# POE.net
KiCad netlist of a schematic drawn in Altium Designer
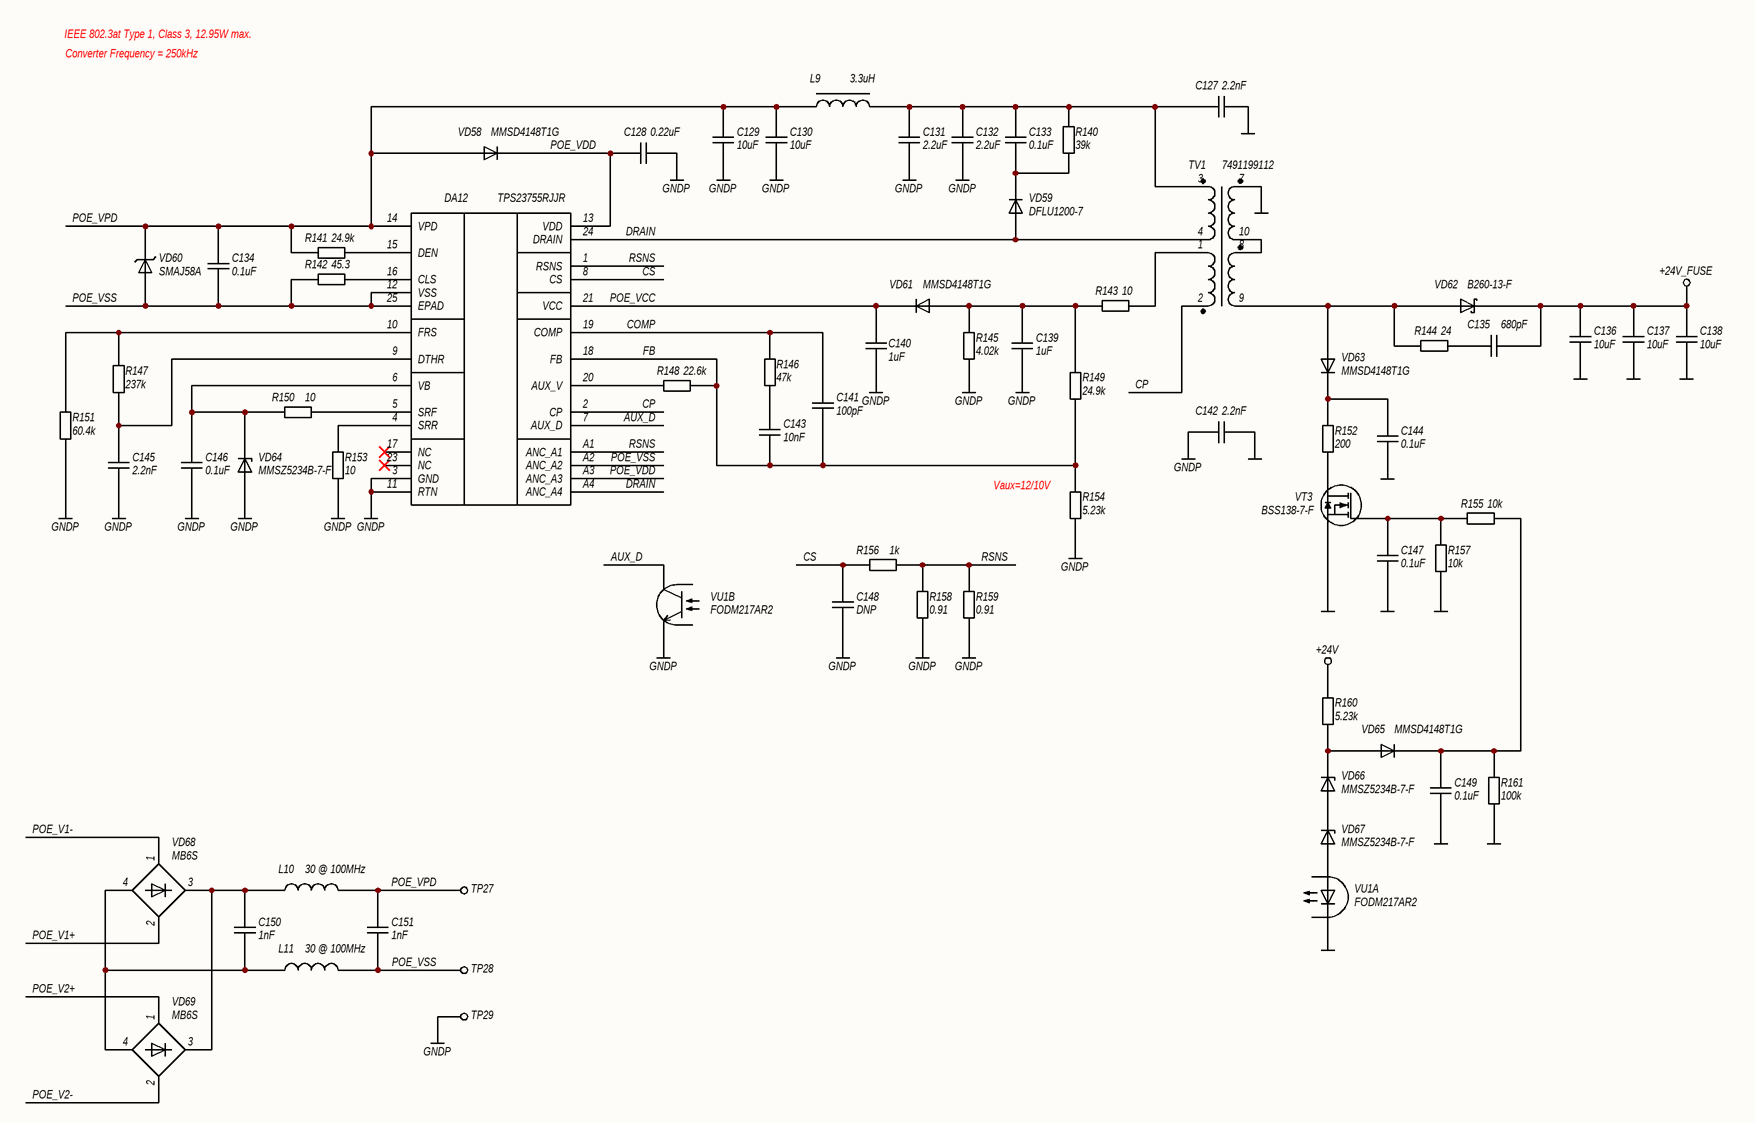
[diagram p0: POE.SchDoc]

(export (version "E")
  (design (tool "Eeschema 10.0.6"))
  (components
    (comp (ref "C127")
      (value "2.2nF")
      (footprint "C1812N")
      (description "Конденсатор")
      (libsource (lib "Components Library") (part "CAP_FIXED"))
    )
    (comp (ref "C128")
      (value "0.22uF")
      (footprint "C0805N")
      (description "Конденсатор")
      (libsource (lib "Components Library") (part "CAP_FIXED"))
    )
    (comp (ref "C129")
      (value "10uF")
      (footprint "C1210N")
      (description "Конденсатор")
      (libsource (lib "Components Library") (part "CAP_FIXED"))
    )
    (comp (ref "C130")
      (value "10uF")
      (footprint "C1210N")
      (description "Конденсатор")
      (libsource (lib "Components Library") (part "CAP_FIXED"))
    )
    (comp (ref "C131")
      (value "2.2uF")
      (footprint "C1210N")
      (description "Конденсатор")
      (libsource (lib "Components Library") (part "CAP_FIXED"))
    )
    (comp (ref "C132")
      (value "2.2uF")
      (footprint "C1210N")
      (description "Конденсатор")
      (libsource (lib "Components Library") (part "CAP_FIXED"))
    )
    (comp (ref "C133")
      (value "0.1uF")
      (footprint "C0805N")
      (description "Конденсатор")
      (libsource (lib "Components Library") (part "CAP_FIXED"))
    )
    (comp (ref "C134")
      (value "0.1uF")
      (footprint "C0805N")
      (description "Конденсатор")
      (libsource (lib "Components Library") (part "CAP_FIXED"))
    )
    (comp (ref "C135")
      (value "680pF")
      (footprint "C0805N")
      (description "Конденсатор")
      (libsource (lib "Components Library") (part "CAP_FIXED"))
    )
    (comp (ref "C136")
      (value "10uF")
      (footprint "C1206N")
      (description "Конденсатор")
      (libsource (lib "Components Library") (part "CAP_FIXED"))
    )
    (comp (ref "C137")
      (value "10uF")
      (footprint "C1206N")
      (description "Конденсатор")
      (libsource (lib "Components Library") (part "CAP_FIXED"))
    )
    (comp (ref "C138")
      (value "10uF")
      (footprint "C1206N")
      (description "Конденсатор")
      (libsource (lib "Components Library") (part "CAP_FIXED"))
    )
    (comp (ref "C139")
      (value "1uF")
      (footprint "C0805N")
      (description "Конденсатор")
      (libsource (lib "Components Library") (part "CAP_FIXED"))
    )
    (comp (ref "C140")
      (value "1uF")
      (footprint "C0805N")
      (description "Конденсатор")
      (libsource (lib "Components Library") (part "CAP_FIXED"))
    )
    (comp (ref "C141")
      (value "100pF")
      (footprint "C0603N")
      (description "Конденсатор")
      (libsource (lib "Components Library") (part "CAP_FIXED"))
    )
    (comp (ref "C142")
      (value "2.2nF")
      (footprint "C1812N")
      (description "Конденсатор")
      (libsource (lib "Components Library") (part "CAP_FIXED"))
    )
    (comp (ref "C143")
      (value "10nF")
      (footprint "C0603N")
      (description "Конденсатор")
      (libsource (lib "Components Library") (part "CAP_FIXED"))
    )
    (comp (ref "C144")
      (value "0.1uF")
      (footprint "C0603N")
      (description "Конденсатор")
      (libsource (lib "Components Library") (part "CAP_FIXED"))
    )
    (comp (ref "C145")
      (value "2.2nF")
      (footprint "C0603N")
      (description "Конденсатор")
      (libsource (lib "Components Library") (part "CAP_FIXED"))
    )
    (comp (ref "C146")
      (value "0.1uF")
      (footprint "C0603N")
      (description "Конденсатор")
      (libsource (lib "Components Library") (part "CAP_FIXED"))
    )
    (comp (ref "C147")
      (value "0.1uF")
      (footprint "C0603N")
      (description "Конденсатор")
      (libsource (lib "Components Library") (part "CAP_FIXED"))
    )
    (comp (ref "C148")
      (value "DNP")
      (footprint "C0603N")
      (description "Конденсатор")
      (libsource (lib "Components Library") (part "CAP_FIXED"))
    )
    (comp (ref "C149")
      (value "0.1uF")
      (footprint "C0603N")
      (description "Конденсатор")
      (libsource (lib "Components Library") (part "CAP_FIXED"))
    )
    (comp (ref "C150")
      (value "1nF")
      (footprint "C0603N")
      (description "Конденсатор")
      (libsource (lib "Components Library") (part "CAP_FIXED"))
    )
    (comp (ref "C151")
      (value "1nF")
      (footprint "C0603N")
      (description "Конденсатор")
      (libsource (lib "Components Library") (part "CAP_FIXED"))
    )
    (comp (ref "DA12")
      (value "TPS23755RJJR")
      (footprint "RJJ0023B (VSON-24 EP)")
      (description "Микросхема PoE 802.3at DC-DC контроллера")
      (libsource (lib "Components Library") (part "TPS23755"))
    )
    (comp (ref "L9")
      (value "3.3uH")
      (footprint "SRN3015")
      (description "Дроссель с магнитопроводом")
      (libsource (lib "Components Library") (part "IND_CORE"))
    )
    (comp (ref "L10")
      (value "30 @ 100MHz")
      (footprint "FB0603N")
      (description "Фильтр ЭМП индуктивный")
      (libsource (lib "Components Library") (part "IND_FILTER"))
    )
    (comp (ref "L11")
      (value "30 @ 100MHz")
      (footprint "FB0603N")
      (description "Фильтр ЭМП индуктивный")
      (libsource (lib "Components Library") (part "IND_FILTER"))
    )
    (comp (ref "R140")
      (value "39k")
      (footprint "R0805N")
      (description "Резистор")
      (libsource (lib "") (part "RES_FIXED_1"))
    )
    (comp (ref "R141")
      (value "24.9k")
      (footprint "R0603N")
      (description "Резистор")
      (libsource (lib "") (part "RES_FIXED_2"))
    )
    (comp (ref "R142")
      (value "45.3")
      (footprint "R0603N")
      (description "Резистор")
      (libsource (lib "") (part "RES_FIXED_2"))
    )
    (comp (ref "R143")
      (value "10")
      (footprint "R0805N")
      (description "Резистор")
      (libsource (lib "") (part "RES_FIXED_2"))
    )
    (comp (ref "R144")
      (value "24")
      (footprint "R1206N")
      (description "Резистор")
      (libsource (lib "Components Library") (part "RES_FIXED"))
    )
    (comp (ref "R145")
      (value "4.02k")
      (footprint "R0603N")
      (description "Резистор")
      (libsource (lib "") (part "RES_FIXED_1"))
    )
    (comp (ref "R146")
      (value "47k")
      (footprint "R0603N")
      (description "Резистор")
      (libsource (lib "") (part "RES_FIXED_3"))
    )
    (comp (ref "R147")
      (value "237k")
      (footprint "R0603N")
      (description "Резистор")
      (libsource (lib "") (part "RES_FIXED_3"))
    )
    (comp (ref "R148")
      (value "22.6k")
      (footprint "R0603N")
      (description "Резистор")
      (libsource (lib "Components Library") (part "RES_FIXED"))
    )
    (comp (ref "R149")
      (value "24.9k")
      (footprint "R0603N")
      (description "Резистор")
      (libsource (lib "") (part "RES_FIXED_1"))
    )
    (comp (ref "R150")
      (value "10")
      (footprint "R0603N")
      (description "Резистор")
      (libsource (lib "") (part "RES_FIXED_2"))
    )
    (comp (ref "R151")
      (value "60.4k")
      (footprint "R0603N")
      (description "Резистор")
      (libsource (lib "") (part "RES_FIXED_1"))
    )
    (comp (ref "R152")
      (value "200")
      (footprint "R2512N")
      (description "Резистор")
      (libsource (lib "") (part "RES_FIXED_1"))
    )
    (comp (ref "R153")
      (value "10")
      (footprint "R0603N")
      (description "Резистор")
      (libsource (lib "") (part "RES_FIXED_1"))
    )
    (comp (ref "R154")
      (value "5.23k")
      (footprint "R0603N")
      (description "Резистор")
      (libsource (lib "") (part "RES_FIXED_1"))
    )
    (comp (ref "R155")
      (value "10k")
      (footprint "R0603N")
      (description "Резистор")
      (libsource (lib "") (part "RES_FIXED_2"))
    )
    (comp (ref "R156")
      (value "1k")
      (footprint "R0603N")
      (description "Резистор")
      (libsource (lib "Components Library") (part "RES_FIXED"))
    )
    (comp (ref "R157")
      (value "10k")
      (footprint "R0603N")
      (description "Резистор")
      (libsource (lib "") (part "RES_FIXED_3"))
    )
    (comp (ref "R158")
      (value "0.91")
      (footprint "R1206N")
      (description "Резистор")
      (libsource (lib "") (part "RES_FIXED_1"))
    )
    (comp (ref "R159")
      (value "0.91")
      (footprint "R1206N")
      (description "Резистор")
      (libsource (lib "") (part "RES_FIXED_1"))
    )
    (comp (ref "R160")
      (value "5.23k")
      (footprint "R0603N")
      (description "Резистор")
      (libsource (lib "") (part "RES_FIXED_1"))
    )
    (comp (ref "R161")
      (value "100k")
      (footprint "R0603N")
      (description "Резистор")
      (libsource (lib "") (part "RES_FIXED_3"))
    )
    (comp (ref "TP27")
      (value "TEST_POINT")
      (footprint "TP_RPAD_0.8MM")
      (description "Контрольная точка")
      (libsource (lib "Components Library") (part "TEST_POINT"))
    )
    (comp (ref "TP28")
      (value "TEST_POINT")
      (footprint "TP_RPAD_0.8MM")
      (description "Контрольная точка")
      (libsource (lib "Components Library") (part "TEST_POINT"))
    )
    (comp (ref "TP29")
      (value "TEST_POINT")
      (footprint "TP_RPAD_0.8MM")
      (description "Контрольная точка")
      (libsource (lib "Components Library") (part "TEST_POINT"))
    )
    (comp (ref "TV1")
      (value "7491199112")
      (footprint "7491199112")
      (description "Трансформатор PoE")
      (libsource (lib "Components Library") (part "7491199112"))
    )
    (comp (ref "VD58")
      (value "MMSD4148T1G")
      (footprint "SOD123")
      (description "Диод")
      (libsource (lib "Components Library") (part "DIODE"))
    )
    (comp (ref "VD59")
      (value "DFLU1200-7")
      (footprint "PowerDI123")
      (description "Диод")
      (libsource (lib "Components Library") (part "DIODE"))
    )
    (comp (ref "VD60")
      (value "SMAJ58A")
      (footprint "SMA")
      (description "TVS диод однонаправлвенный")
      (libsource (lib "Components Library") (part "TVS_UNIDIR"))
    )
    (comp (ref "VD61")
      (value "MMSD4148T1G")
      (footprint "SOD123")
      (description "Диод")
      (libsource (lib "Components Library") (part "DIODE"))
    )
    (comp (ref "VD62")
      (value "B260-13-F")
      (footprint "SMB")
      (description "Диод Шоттки")
      (libsource (lib "Components Library") (part "SCHOTTKY"))
    )
    (comp (ref "VD63")
      (value "MMSD4148T1G")
      (footprint "SOD123")
      (description "Диод")
      (libsource (lib "Components Library") (part "DIODE"))
    )
    (comp (ref "VD64")
      (value "MMSZ5234B-7-F")
      (footprint "SOD123")
      (description "Стабилитрон")
      (libsource (lib "Components Library") (part "ZENER"))
    )
    (comp (ref "VD65")
      (value "MMSD4148T1G")
      (footprint "SOD123")
      (description "Диод")
      (libsource (lib "Components Library") (part "DIODE"))
    )
    (comp (ref "VD66")
      (value "MMSZ5234B-7-F")
      (footprint "SOD123")
      (description "Стабилитрон")
      (libsource (lib "Components Library") (part "ZENER"))
    )
    (comp (ref "VD67")
      (value "MMSZ5234B-7-F")
      (footprint "SOD123")
      (description "Стабилитрон")
      (libsource (lib "Components Library") (part "ZENER"))
    )
    (comp (ref "VD68")
      (value "MB6S")
      (footprint "MBS (TO-269AA)")
      (description "Диодный мост, однофазный")
      (libsource (lib "Components Library") (part "DIODE_BRIDGE_1PH"))
    )
    (comp (ref "VD69")
      (value "MB6S")
      (footprint "MBS (TO-269AA)")
      (description "Диодный мост, однофазный")
      (libsource (lib "Components Library") (part "DIODE_BRIDGE_1PH"))
    )
    (comp (ref "VT3")
      (value "BSS138-7-F")
      (footprint "SOT23")
      (description "МОП транзистор, N-канальный")
      (libsource (lib "Components Library") (part "N-MOS 3 LEADS_G1"))
    )
    (comp (ref "VU1")
      (value "FODM217AR2")
      (footprint "MFP4 2.5x4.4")
      (description "NPN транзисторная оптопара")
      (libsource (lib "Components Library") (part "OPTOCPL_NPN"))
    )
  )
  (nets
    (net (code "1") (name "+24V") (class "Default")
      (node (ref "R160") (pin "2") (pinfunction "2_2") (pintype "passive"))
    )
    (net (code "2") (name "+24V_FUSE") (class "Default")
      (node (ref "C135") (pin "2") (pinfunction "2_2") (pintype "passive"))
      (node (ref "C136") (pin "2") (pinfunction "2_2") (pintype "passive"))
      (node (ref "C137") (pin "2") (pinfunction "2_2") (pintype "passive"))
      (node (ref "C138") (pin "2") (pinfunction "2_2") (pintype "passive"))
      (node (ref "VD62") (pin "1") (pinfunction "K_1") (pintype "passive"))
    )
    (net (code "3") (name "/AUX_D") (class "Default")
      (node (ref "DA12") (pin "7") (pinfunction "AUX_D_7") (pintype "passive"))
      (node (ref "VU1") (pin "4") (pinfunction "C_4") (pintype "passive"))
    )
    (net (code "4") (name "/COMP") (class "Default")
      (node (ref "C141") (pin "1") (pinfunction "1_1") (pintype "passive"))
      (node (ref "DA12") (pin "19") (pinfunction "COMP_19") (pintype "passive"))
      (node (ref "R146") (pin "1") (pinfunction "1_1") (pintype "passive"))
    )
    (net (code "5") (name "/CP") (class "Default")
      (node (ref "DA12") (pin "2") (pinfunction "CP_2") (pintype "passive"))
      (node (ref "TV1") (pin "2") (pintype "power_in"))
    )
    (net (code "6") (name "/CS") (class "Default")
      (node (ref "C148") (pin "1") (pinfunction "1_1") (pintype "passive"))
      (node (ref "DA12") (pin "8") (pinfunction "CS_8") (pintype "passive"))
      (node (ref "R156") (pin "2") (pinfunction "2_2") (pintype "passive"))
    )
    (net (code "7") (name "/DRAIN") (class "Default")
      (node (ref "DA12") (pin "24") (pinfunction "DRAIN_24") (pintype "passive"))
      (node (ref "DA12") (pin "A4") (pinfunction "ANC_A4_A4") (pintype "passive"))
      (node (ref "TV1") (pin "4") (pintype "power_in"))
      (node (ref "VD59") (pin "2") (pinfunction "A_2") (pintype "passive"))
    )
    (net (code "8") (name "/FB") (class "Default")
      (node (ref "C141") (pin "2") (pinfunction "2_2") (pintype "passive"))
      (node (ref "C143") (pin "2") (pinfunction "2_2") (pintype "passive"))
      (node (ref "DA12") (pin "18") (pinfunction "FB_18") (pintype "passive"))
      (node (ref "R148") (pin "1") (pinfunction "1_1") (pintype "passive"))
      (node (ref "R149") (pin "1") (pinfunction "1_1") (pintype "passive"))
      (node (ref "R154") (pin "2") (pinfunction "2_2") (pintype "passive"))
    )
    (net (code "9") (name "/POE_V1+") (class "Default")
      (node (ref "VD68") (pin "2") (pinfunction "AC_2") (pintype "power_in"))
    )
    (net (code "10") (name "/POE_V1-") (class "Default")
      (node (ref "VD68") (pin "1") (pinfunction "AC_1") (pintype "power_in"))
    )
    (net (code "11") (name "/POE_V2+") (class "Default")
      (node (ref "VD69") (pin "1") (pinfunction "AC_1") (pintype "power_in"))
    )
    (net (code "12") (name "/POE_V2-") (class "Default")
      (node (ref "VD69") (pin "2") (pinfunction "AC_2") (pintype "power_in"))
    )
    (net (code "13") (name "/POE_VCC") (class "Default")
      (node (ref "C140") (pin "2") (pinfunction "2_2") (pintype "passive"))
      (node (ref "DA12") (pin "21") (pinfunction "VCC_21") (pintype "passive"))
      (node (ref "VD61") (pin "1") (pinfunction "K_1") (pintype "passive"))
    )
    (net (code "14") (name "/POE_VDD") (class "Default")
      (node (ref "C128") (pin "2") (pinfunction "2_2") (pintype "passive"))
      (node (ref "DA12") (pin "13") (pinfunction "VDD_13") (pintype "passive"))
      (node (ref "DA12") (pin "A3") (pinfunction "ANC_A3_A3") (pintype "passive"))
      (node (ref "VD58") (pin "1") (pinfunction "K_1") (pintype "passive"))
    )
    (net (code "15") (name "/POE_VPD") (class "Default")
      (node (ref "C129") (pin "2") (pinfunction "2_2") (pintype "passive"))
      (node (ref "C130") (pin "2") (pinfunction "2_2") (pintype "passive"))
      (node (ref "C134") (pin "2") (pinfunction "2_2") (pintype "passive"))
      (node (ref "C151") (pin "1") (pinfunction "1_1") (pintype "passive"))
      (node (ref "DA12") (pin "14") (pinfunction "VPD_14") (pintype "passive"))
      (node (ref "L10") (pin "2") (pinfunction "2_2") (pintype "passive"))
      (node (ref "L9") (pin "1") (pinfunction "1_1") (pintype "passive"))
      (node (ref "R141") (pin "1") (pinfunction "1_1") (pintype "passive"))
      (node (ref "TP27") (pin "1") (pinfunction "1_1") (pintype "passive"))
      (node (ref "VD58") (pin "2") (pinfunction "A_2") (pintype "passive"))
      (node (ref "VD60") (pin "1") (pinfunction "K_1") (pintype "passive"))
    )
    (net (code "16") (name "/POE_VSS") (class "Default")
      (node (ref "C134") (pin "1") (pinfunction "1_1") (pintype "passive"))
      (node (ref "C151") (pin "2") (pinfunction "2_2") (pintype "passive"))
      (node (ref "DA12") (pin "12") (pinfunction "VSS_12") (pintype "passive"))
      (node (ref "DA12") (pin "25") (pinfunction "EPAD_25") (pintype "passive"))
      (node (ref "DA12") (pin "A2") (pinfunction "ANC_A2_A2") (pintype "passive"))
      (node (ref "L11") (pin "2") (pinfunction "2_2") (pintype "passive"))
      (node (ref "R142") (pin "1") (pinfunction "1_1") (pintype "passive"))
      (node (ref "TP28") (pin "1") (pinfunction "1_1") (pintype "passive"))
      (node (ref "VD60") (pin "2") (pinfunction "A_2") (pintype "passive"))
    )
    (net (code "17") (name "/RSNS") (class "Default")
      (node (ref "DA12") (pin "1") (pinfunction "RSNS_1") (pintype "passive"))
      (node (ref "DA12") (pin "A1") (pinfunction "ANC_A1_A1") (pintype "passive"))
      (node (ref "R156") (pin "1") (pinfunction "1_1") (pintype "passive"))
      (node (ref "R158") (pin "2") (pinfunction "2_2") (pintype "passive"))
      (node (ref "R159") (pin "2") (pinfunction "2_2") (pintype "passive"))
    )
    (net (code "18") (name "GND") (class "Default")
      (node (ref "C127") (pin "2") (pinfunction "2_2") (pintype "passive"))
      (node (ref "C136") (pin "1") (pinfunction "1_1") (pintype "passive"))
      (node (ref "C137") (pin "1") (pinfunction "1_1") (pintype "passive"))
      (node (ref "C138") (pin "1") (pinfunction "1_1") (pintype "passive"))
      (node (ref "C142") (pin "2") (pinfunction "2_2") (pintype "passive"))
      (node (ref "C144") (pin "2") (pinfunction "2_2") (pintype "passive"))
      (node (ref "C147") (pin "1") (pinfunction "1_1") (pintype "passive"))
      (node (ref "C149") (pin "1") (pinfunction "1_1") (pintype "passive"))
      (node (ref "R157") (pin "2") (pinfunction "2_2") (pintype "passive"))
      (node (ref "R161") (pin "2") (pinfunction "2_2") (pintype "passive"))
      (node (ref "TV1") (pin "7") (pintype "power_in"))
      (node (ref "VT3") (pin "2") (pinfunction "S_2") (pintype "passive"))
      (node (ref "VU1") (pin "2") (pinfunction "K_2") (pintype "passive"))
    )
    (net (code "19") (name "GNDP") (class "Default")
      (node (ref "C128") (pin "1") (pinfunction "1_1") (pintype "passive"))
      (node (ref "C129") (pin "1") (pinfunction "1_1") (pintype "passive"))
      (node (ref "C130") (pin "1") (pinfunction "1_1") (pintype "passive"))
      (node (ref "C131") (pin "1") (pinfunction "1_1") (pintype "passive"))
      (node (ref "C132") (pin "1") (pinfunction "1_1") (pintype "passive"))
      (node (ref "C139") (pin "1") (pinfunction "1_1") (pintype "passive"))
      (node (ref "C140") (pin "1") (pinfunction "1_1") (pintype "passive"))
      (node (ref "C142") (pin "1") (pinfunction "1_1") (pintype "passive"))
      (node (ref "C145") (pin "1") (pinfunction "1_1") (pintype "passive"))
      (node (ref "C146") (pin "2") (pinfunction "2_2") (pintype "passive"))
      (node (ref "C148") (pin "2") (pinfunction "2_2") (pintype "passive"))
      (node (ref "DA12") (pin "11") (pinfunction "RTN_11") (pintype "passive"))
      (node (ref "DA12") (pin "3") (pinfunction "GND_3") (pintype "passive"))
      (node (ref "R145") (pin "1") (pinfunction "1_1") (pintype "passive"))
      (node (ref "R151") (pin "1") (pinfunction "1_1") (pintype "passive"))
      (node (ref "R153") (pin "1") (pinfunction "1_1") (pintype "passive"))
      (node (ref "R154") (pin "1") (pinfunction "1_1") (pintype "passive"))
      (node (ref "R158") (pin "1") (pinfunction "1_1") (pintype "passive"))
      (node (ref "R159") (pin "1") (pinfunction "1_1") (pintype "passive"))
      (node (ref "TP29") (pin "1") (pinfunction "1_1") (pintype "passive"))
      (node (ref "VD64") (pin "2") (pinfunction "A_2") (pintype "passive"))
      (node (ref "VU1") (pin "3") (pinfunction "E_3") (pintype "passive"))
    )
    (net (code "20") (name "Net-(C127-Pad1)") (class "Default")
      (node (ref "C127") (pin "1") (pinfunction "1_1") (pintype "passive"))
      (node (ref "C131") (pin "2") (pinfunction "2_2") (pintype "passive"))
      (node (ref "C132") (pin "2") (pinfunction "2_2") (pintype "passive"))
      (node (ref "C133") (pin "2") (pinfunction "2_2") (pintype "passive"))
      (node (ref "L9") (pin "2") (pinfunction "2_2") (pintype "passive"))
      (node (ref "R140") (pin "2") (pinfunction "2_2") (pintype "passive"))
      (node (ref "TV1") (pin "3") (pintype "power_in"))
    )
    (net (code "21") (name "Net-(C135-Pad1)") (class "Default")
      (node (ref "C135") (pin "1") (pinfunction "1_1") (pintype "passive"))
      (node (ref "R144") (pin "1") (pinfunction "1_1") (pintype "passive"))
    )
    (net (code "22") (name "Net-(C143-Pad1)") (class "Default")
      (node (ref "C143") (pin "1") (pinfunction "1_1") (pintype "passive"))
      (node (ref "R146") (pin "2") (pinfunction "2_2") (pintype "passive"))
    )
    (net (code "23") (name "Net-(DA12-AUX_V)") (class "Default")
      (node (ref "DA12") (pin "20") (pinfunction "AUX_V_20") (pintype "passive"))
      (node (ref "R148") (pin "2") (pinfunction "2_2") (pintype "passive"))
    )
    (net (code "24") (name "Net-(DA12-CLS)") (class "Default")
      (node (ref "DA12") (pin "16") (pinfunction "CLS_16") (pintype "passive"))
      (node (ref "R142") (pin "2") (pinfunction "2_2") (pintype "passive"))
    )
    (net (code "25") (name "Net-(DA12-DEN)") (class "Default")
      (node (ref "DA12") (pin "15") (pinfunction "DEN_15") (pintype "passive"))
      (node (ref "R141") (pin "2") (pinfunction "2_2") (pintype "passive"))
    )
    (net (code "26") (name "Net-(DA12-DTHR)") (class "Default")
      (node (ref "C145") (pin "2") (pinfunction "2_2") (pintype "passive"))
      (node (ref "DA12") (pin "9") (pinfunction "DTHR_9") (pintype "passive"))
      (node (ref "R147") (pin "2") (pinfunction "2_2") (pintype "passive"))
    )
    (net (code "27") (name "Net-(DA12-FRS)") (class "Default")
      (node (ref "DA12") (pin "10") (pinfunction "FRS_10") (pintype "passive"))
      (node (ref "R147") (pin "1") (pinfunction "1_1") (pintype "passive"))
      (node (ref "R151") (pin "2") (pinfunction "2_2") (pintype "passive"))
    )
    (net (code "28") (name "Net-(DA12-SRF)") (class "Default")
      (node (ref "DA12") (pin "5") (pinfunction "SRF_5") (pintype "passive"))
      (node (ref "R150") (pin "2") (pinfunction "2_2") (pintype "passive"))
    )
    (net (code "29") (name "Net-(DA12-SRR)") (class "Default")
      (node (ref "DA12") (pin "4") (pinfunction "SRR_4") (pintype "passive"))
      (node (ref "R153") (pin "2") (pinfunction "2_2") (pintype "passive"))
    )
    (net (code "30") (name "Net-(DA12-VB)") (class "Default")
      (node (ref "C146") (pin "1") (pinfunction "1_1") (pintype "passive"))
      (node (ref "DA12") (pin "6") (pinfunction "VB_6") (pintype "passive"))
      (node (ref "R150") (pin "1") (pinfunction "1_1") (pintype "passive"))
      (node (ref "VD64") (pin "1") (pinfunction "K_1") (pintype "passive"))
    )
    (net (code "31") (name "Net-(R143-Pad2)") (class "Default")
      (node (ref "R143") (pin "2") (pinfunction "2_2") (pintype "passive"))
      (node (ref "TV1") (pin "1") (pintype "power_in"))
    )
    (net (code "32") (name "Net-(TV1-Pad10)") (class "Default")
      (node (ref "TV1") (pin "10") (pintype "power_in"))
      (node (ref "TV1") (pin "8") (pintype "power_in"))
    )
    (net (code "33") (name "Net-(VD59-K)") (class "Default")
      (node (ref "C133") (pin "1") (pinfunction "1_1") (pintype "passive"))
      (node (ref "R140") (pin "1") (pinfunction "1_1") (pintype "passive"))
      (node (ref "VD59") (pin "1") (pinfunction "K_1") (pintype "passive"))
    )
    (net (code "34") (name "Net-(VD61-A)") (class "Default")
      (node (ref "C139") (pin "2") (pinfunction "2_2") (pintype "passive"))
      (node (ref "R143") (pin "1") (pinfunction "1_1") (pintype "passive"))
      (node (ref "R145") (pin "2") (pinfunction "2_2") (pintype "passive"))
      (node (ref "R149") (pin "2") (pinfunction "2_2") (pintype "passive"))
      (node (ref "VD61") (pin "2") (pinfunction "A_2") (pintype "passive"))
    )
    (net (code "35") (name "Net-(VD62-A)") (class "Default")
      (node (ref "R144") (pin "2") (pinfunction "2_2") (pintype "passive"))
      (node (ref "TV1") (pin "9") (pintype "power_in"))
      (node (ref "VD62") (pin "2") (pinfunction "A_2") (pintype "passive"))
      (node (ref "VD63") (pin "2") (pinfunction "A_2") (pintype "passive"))
    )
    (net (code "36") (name "Net-(VD63-K)") (class "Default")
      (node (ref "C144") (pin "1") (pinfunction "1_1") (pintype "passive"))
      (node (ref "R152") (pin "2") (pinfunction "2_2") (pintype "passive"))
      (node (ref "VD63") (pin "1") (pinfunction "K_1") (pintype "passive"))
    )
    (net (code "37") (name "Net-(VD65-A)") (class "Default")
      (node (ref "R160") (pin "1") (pinfunction "1_1") (pintype "passive"))
      (node (ref "VD65") (pin "2") (pinfunction "A_2") (pintype "passive"))
      (node (ref "VD66") (pin "1") (pinfunction "K_1") (pintype "passive"))
    )
    (net (code "38") (name "Net-(VD65-K)") (class "Default")
      (node (ref "C149") (pin "2") (pinfunction "2_2") (pintype "passive"))
      (node (ref "R155") (pin "2") (pinfunction "2_2") (pintype "passive"))
      (node (ref "R161") (pin "1") (pinfunction "1_1") (pintype "passive"))
      (node (ref "VD65") (pin "1") (pinfunction "K_1") (pintype "passive"))
    )
    (net (code "39") (name "Net-(VD66-A)") (class "Default")
      (node (ref "VD66") (pin "2") (pinfunction "A_2") (pintype "passive"))
      (node (ref "VD67") (pin "1") (pinfunction "K_1") (pintype "passive"))
    )
    (net (code "40") (name "Net-(VD67-A)") (class "Default")
      (node (ref "VD67") (pin "2") (pinfunction "A_2") (pintype "passive"))
      (node (ref "VU1") (pin "1") (pinfunction "A_1") (pintype "passive"))
    )
    (net (code "41") (name "Net-(VD68-+)") (class "Default")
      (node (ref "C150") (pin "1") (pinfunction "1_1") (pintype "passive"))
      (node (ref "L10") (pin "1") (pinfunction "1_1") (pintype "passive"))
      (node (ref "VD68") (pin "3") (pinfunction "+_3") (pintype "power_in"))
      (node (ref "VD69") (pin "3") (pinfunction "+_3") (pintype "power_in"))
    )
    (net (code "42") (name "Net-(VD68--)") (class "Default")
      (node (ref "C150") (pin "2") (pinfunction "2_2") (pintype "passive"))
      (node (ref "L11") (pin "1") (pinfunction "1_1") (pintype "passive"))
      (node (ref "VD68") (pin "4") (pinfunction "-_4") (pintype "power_in"))
      (node (ref "VD69") (pin "4") (pinfunction "-_4") (pintype "power_in"))
    )
    (net (code "43") (name "Net-(VT3-D)") (class "Default")
      (node (ref "R152") (pin "1") (pinfunction "1_1") (pintype "passive"))
      (node (ref "VT3") (pin "3") (pinfunction "D_3") (pintype "passive"))
    )
    (net (code "44") (name "Net-(VT3-G)") (class "Default")
      (node (ref "C147") (pin "2") (pinfunction "2_2") (pintype "passive"))
      (node (ref "R155") (pin "1") (pinfunction "1_1") (pintype "passive"))
      (node (ref "R157") (pin "1") (pinfunction "1_1") (pintype "passive"))
      (node (ref "VT3") (pin "1") (pinfunction "G_1") (pintype "passive"))
    )
    (net (code "45") (name "unconnected-(DA12-NC-Pad17)") (class "Default")
      (node (ref "DA12") (pin "17") (pinfunction "NC_17") (pintype "passive+no_connect"))
    )
    (net (code "46") (name "unconnected-(DA12-NC-Pad23)") (class "Default")
      (node (ref "DA12") (pin "23") (pinfunction "NC_23") (pintype "passive+no_connect"))
    )
  )
)
